# tongue_electrode_grid.net
KiCad netlist of a schematic drawn in EAGLE
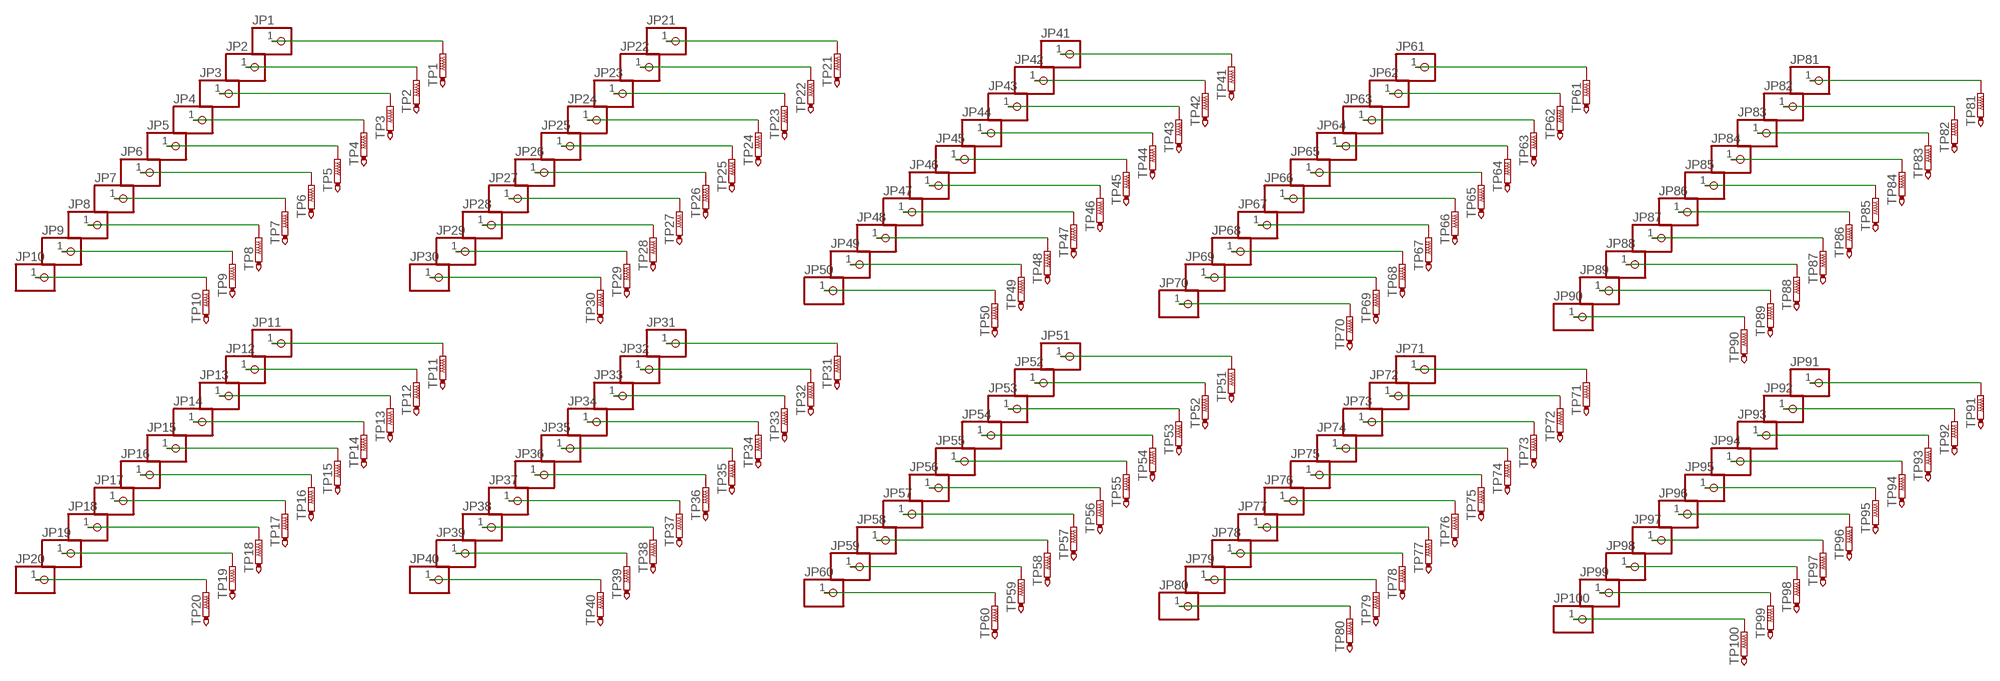
[diagram p0: schematic, sheet 1]

(export (version "E")
  (design (tool "Eeschema 10.0.6"))
  (components
    (comp (ref "JP1")
      (value "PINHD-1X1")
      (footprint "eagle-import:1X01")
      (libsource (lib "eagle-import") (part "PINHD-1X1"))
    )
    (comp (ref "JP2")
      (value "PINHD-1X1")
      (footprint "eagle-import:1X01")
      (libsource (lib "eagle-import") (part "PINHD-1X1"))
    )
    (comp (ref "JP3")
      (value "PINHD-1X1")
      (footprint "eagle-import:1X01")
      (libsource (lib "eagle-import") (part "PINHD-1X1"))
    )
    (comp (ref "JP4")
      (value "PINHD-1X1")
      (footprint "eagle-import:1X01")
      (libsource (lib "eagle-import") (part "PINHD-1X1"))
    )
    (comp (ref "JP5")
      (value "PINHD-1X1")
      (footprint "eagle-import:1X01")
      (libsource (lib "eagle-import") (part "PINHD-1X1"))
    )
    (comp (ref "JP6")
      (value "PINHD-1X1")
      (footprint "eagle-import:1X01")
      (libsource (lib "eagle-import") (part "PINHD-1X1"))
    )
    (comp (ref "JP7")
      (value "PINHD-1X1")
      (footprint "eagle-import:1X01")
      (libsource (lib "eagle-import") (part "PINHD-1X1"))
    )
    (comp (ref "JP8")
      (value "PINHD-1X1")
      (footprint "eagle-import:1X01")
      (libsource (lib "eagle-import") (part "PINHD-1X1"))
    )
    (comp (ref "JP9")
      (value "PINHD-1X1")
      (footprint "eagle-import:1X01")
      (libsource (lib "eagle-import") (part "PINHD-1X1"))
    )
    (comp (ref "JP10")
      (value "PINHD-1X1")
      (footprint "eagle-import:1X01")
      (libsource (lib "eagle-import") (part "PINHD-1X1"))
    )
    (comp (ref "JP11")
      (value "PINHD-1X1")
      (footprint "eagle-import:1X01")
      (libsource (lib "eagle-import") (part "PINHD-1X1"))
    )
    (comp (ref "JP12")
      (value "PINHD-1X1")
      (footprint "eagle-import:1X01")
      (libsource (lib "eagle-import") (part "PINHD-1X1"))
    )
    (comp (ref "JP13")
      (value "PINHD-1X1")
      (footprint "eagle-import:1X01")
      (libsource (lib "eagle-import") (part "PINHD-1X1"))
    )
    (comp (ref "JP14")
      (value "PINHD-1X1")
      (footprint "eagle-import:1X01")
      (libsource (lib "eagle-import") (part "PINHD-1X1"))
    )
    (comp (ref "JP15")
      (value "PINHD-1X1")
      (footprint "eagle-import:1X01")
      (libsource (lib "eagle-import") (part "PINHD-1X1"))
    )
    (comp (ref "JP16")
      (value "PINHD-1X1")
      (footprint "eagle-import:1X01")
      (libsource (lib "eagle-import") (part "PINHD-1X1"))
    )
    (comp (ref "JP17")
      (value "PINHD-1X1")
      (footprint "eagle-import:1X01")
      (libsource (lib "eagle-import") (part "PINHD-1X1"))
    )
    (comp (ref "JP18")
      (value "PINHD-1X1")
      (footprint "eagle-import:1X01")
      (libsource (lib "eagle-import") (part "PINHD-1X1"))
    )
    (comp (ref "JP19")
      (value "PINHD-1X1")
      (footprint "eagle-import:1X01")
      (libsource (lib "eagle-import") (part "PINHD-1X1"))
    )
    (comp (ref "JP20")
      (value "PINHD-1X1")
      (footprint "eagle-import:1X01")
      (libsource (lib "eagle-import") (part "PINHD-1X1"))
    )
    (comp (ref "JP21")
      (value "PINHD-1X1")
      (footprint "eagle-import:1X01")
      (libsource (lib "eagle-import") (part "PINHD-1X1"))
    )
    (comp (ref "JP22")
      (value "PINHD-1X1")
      (footprint "eagle-import:1X01")
      (libsource (lib "eagle-import") (part "PINHD-1X1"))
    )
    (comp (ref "JP23")
      (value "PINHD-1X1")
      (footprint "eagle-import:1X01")
      (libsource (lib "eagle-import") (part "PINHD-1X1"))
    )
    (comp (ref "JP24")
      (value "PINHD-1X1")
      (footprint "eagle-import:1X01")
      (libsource (lib "eagle-import") (part "PINHD-1X1"))
    )
    (comp (ref "JP25")
      (value "PINHD-1X1")
      (footprint "eagle-import:1X01")
      (libsource (lib "eagle-import") (part "PINHD-1X1"))
    )
    (comp (ref "JP26")
      (value "PINHD-1X1")
      (footprint "eagle-import:1X01")
      (libsource (lib "eagle-import") (part "PINHD-1X1"))
    )
    (comp (ref "JP27")
      (value "PINHD-1X1")
      (footprint "eagle-import:1X01")
      (libsource (lib "eagle-import") (part "PINHD-1X1"))
    )
    (comp (ref "JP28")
      (value "PINHD-1X1")
      (footprint "eagle-import:1X01")
      (libsource (lib "eagle-import") (part "PINHD-1X1"))
    )
    (comp (ref "JP29")
      (value "PINHD-1X1")
      (footprint "eagle-import:1X01")
      (libsource (lib "eagle-import") (part "PINHD-1X1"))
    )
    (comp (ref "JP30")
      (value "PINHD-1X1")
      (footprint "eagle-import:1X01")
      (libsource (lib "eagle-import") (part "PINHD-1X1"))
    )
    (comp (ref "JP31")
      (value "PINHD-1X1")
      (footprint "eagle-import:1X01")
      (libsource (lib "eagle-import") (part "PINHD-1X1"))
    )
    (comp (ref "JP32")
      (value "PINHD-1X1")
      (footprint "eagle-import:1X01")
      (libsource (lib "eagle-import") (part "PINHD-1X1"))
    )
    (comp (ref "JP33")
      (value "PINHD-1X1")
      (footprint "eagle-import:1X01")
      (libsource (lib "eagle-import") (part "PINHD-1X1"))
    )
    (comp (ref "JP34")
      (value "PINHD-1X1")
      (footprint "eagle-import:1X01")
      (libsource (lib "eagle-import") (part "PINHD-1X1"))
    )
    (comp (ref "JP35")
      (value "PINHD-1X1")
      (footprint "eagle-import:1X01")
      (libsource (lib "eagle-import") (part "PINHD-1X1"))
    )
    (comp (ref "JP36")
      (value "PINHD-1X1")
      (footprint "eagle-import:1X01")
      (libsource (lib "eagle-import") (part "PINHD-1X1"))
    )
    (comp (ref "JP37")
      (value "PINHD-1X1")
      (footprint "eagle-import:1X01")
      (libsource (lib "eagle-import") (part "PINHD-1X1"))
    )
    (comp (ref "JP38")
      (value "PINHD-1X1")
      (footprint "eagle-import:1X01")
      (libsource (lib "eagle-import") (part "PINHD-1X1"))
    )
    (comp (ref "JP39")
      (value "PINHD-1X1")
      (footprint "eagle-import:1X01")
      (libsource (lib "eagle-import") (part "PINHD-1X1"))
    )
    (comp (ref "JP40")
      (value "PINHD-1X1")
      (footprint "eagle-import:1X01")
      (libsource (lib "eagle-import") (part "PINHD-1X1"))
    )
    (comp (ref "JP41")
      (value "PINHD-1X1")
      (footprint "eagle-import:1X01")
      (libsource (lib "eagle-import") (part "PINHD-1X1"))
    )
    (comp (ref "JP42")
      (value "PINHD-1X1")
      (footprint "eagle-import:1X01")
      (libsource (lib "eagle-import") (part "PINHD-1X1"))
    )
    (comp (ref "JP43")
      (value "PINHD-1X1")
      (footprint "eagle-import:1X01")
      (libsource (lib "eagle-import") (part "PINHD-1X1"))
    )
    (comp (ref "JP44")
      (value "PINHD-1X1")
      (footprint "eagle-import:1X01")
      (libsource (lib "eagle-import") (part "PINHD-1X1"))
    )
    (comp (ref "JP45")
      (value "PINHD-1X1")
      (footprint "eagle-import:1X01")
      (libsource (lib "eagle-import") (part "PINHD-1X1"))
    )
    (comp (ref "JP46")
      (value "PINHD-1X1")
      (footprint "eagle-import:1X01")
      (libsource (lib "eagle-import") (part "PINHD-1X1"))
    )
    (comp (ref "JP47")
      (value "PINHD-1X1")
      (footprint "eagle-import:1X01")
      (libsource (lib "eagle-import") (part "PINHD-1X1"))
    )
    (comp (ref "JP48")
      (value "PINHD-1X1")
      (footprint "eagle-import:1X01")
      (libsource (lib "eagle-import") (part "PINHD-1X1"))
    )
    (comp (ref "JP49")
      (value "PINHD-1X1")
      (footprint "eagle-import:1X01")
      (libsource (lib "eagle-import") (part "PINHD-1X1"))
    )
    (comp (ref "JP50")
      (value "PINHD-1X1")
      (footprint "eagle-import:1X01")
      (libsource (lib "eagle-import") (part "PINHD-1X1"))
    )
    (comp (ref "JP51")
      (value "PINHD-1X1")
      (footprint "eagle-import:1X01")
      (libsource (lib "eagle-import") (part "PINHD-1X1"))
    )
    (comp (ref "JP52")
      (value "PINHD-1X1")
      (footprint "eagle-import:1X01")
      (libsource (lib "eagle-import") (part "PINHD-1X1"))
    )
    (comp (ref "JP53")
      (value "PINHD-1X1")
      (footprint "eagle-import:1X01")
      (libsource (lib "eagle-import") (part "PINHD-1X1"))
    )
    (comp (ref "JP54")
      (value "PINHD-1X1")
      (footprint "eagle-import:1X01")
      (libsource (lib "eagle-import") (part "PINHD-1X1"))
    )
    (comp (ref "JP55")
      (value "PINHD-1X1")
      (footprint "eagle-import:1X01")
      (libsource (lib "eagle-import") (part "PINHD-1X1"))
    )
    (comp (ref "JP56")
      (value "PINHD-1X1")
      (footprint "eagle-import:1X01")
      (libsource (lib "eagle-import") (part "PINHD-1X1"))
    )
    (comp (ref "JP57")
      (value "PINHD-1X1")
      (footprint "eagle-import:1X01")
      (libsource (lib "eagle-import") (part "PINHD-1X1"))
    )
    (comp (ref "JP58")
      (value "PINHD-1X1")
      (footprint "eagle-import:1X01")
      (libsource (lib "eagle-import") (part "PINHD-1X1"))
    )
    (comp (ref "JP59")
      (value "PINHD-1X1")
      (footprint "eagle-import:1X01")
      (libsource (lib "eagle-import") (part "PINHD-1X1"))
    )
    (comp (ref "JP60")
      (value "PINHD-1X1")
      (footprint "eagle-import:1X01")
      (libsource (lib "eagle-import") (part "PINHD-1X1"))
    )
    (comp (ref "JP61")
      (value "PINHD-1X1")
      (footprint "eagle-import:1X01")
      (libsource (lib "eagle-import") (part "PINHD-1X1"))
    )
    (comp (ref "JP62")
      (value "PINHD-1X1")
      (footprint "eagle-import:1X01")
      (libsource (lib "eagle-import") (part "PINHD-1X1"))
    )
    (comp (ref "JP63")
      (value "PINHD-1X1")
      (footprint "eagle-import:1X01")
      (libsource (lib "eagle-import") (part "PINHD-1X1"))
    )
    (comp (ref "JP64")
      (value "PINHD-1X1")
      (footprint "eagle-import:1X01")
      (libsource (lib "eagle-import") (part "PINHD-1X1"))
    )
    (comp (ref "JP65")
      (value "PINHD-1X1")
      (footprint "eagle-import:1X01")
      (libsource (lib "eagle-import") (part "PINHD-1X1"))
    )
    (comp (ref "JP66")
      (value "PINHD-1X1")
      (footprint "eagle-import:1X01")
      (libsource (lib "eagle-import") (part "PINHD-1X1"))
    )
    (comp (ref "JP67")
      (value "PINHD-1X1")
      (footprint "eagle-import:1X01")
      (libsource (lib "eagle-import") (part "PINHD-1X1"))
    )
    (comp (ref "JP68")
      (value "PINHD-1X1")
      (footprint "eagle-import:1X01")
      (libsource (lib "eagle-import") (part "PINHD-1X1"))
    )
    (comp (ref "JP69")
      (value "PINHD-1X1")
      (footprint "eagle-import:1X01")
      (libsource (lib "eagle-import") (part "PINHD-1X1"))
    )
    (comp (ref "JP70")
      (value "PINHD-1X1")
      (footprint "eagle-import:1X01")
      (libsource (lib "eagle-import") (part "PINHD-1X1"))
    )
    (comp (ref "JP71")
      (value "PINHD-1X1")
      (footprint "eagle-import:1X01")
      (libsource (lib "eagle-import") (part "PINHD-1X1"))
    )
    (comp (ref "JP72")
      (value "PINHD-1X1")
      (footprint "eagle-import:1X01")
      (libsource (lib "eagle-import") (part "PINHD-1X1"))
    )
    (comp (ref "JP73")
      (value "PINHD-1X1")
      (footprint "eagle-import:1X01")
      (libsource (lib "eagle-import") (part "PINHD-1X1"))
    )
    (comp (ref "JP74")
      (value "PINHD-1X1")
      (footprint "eagle-import:1X01")
      (libsource (lib "eagle-import") (part "PINHD-1X1"))
    )
    (comp (ref "JP75")
      (value "PINHD-1X1")
      (footprint "eagle-import:1X01")
      (libsource (lib "eagle-import") (part "PINHD-1X1"))
    )
    (comp (ref "JP76")
      (value "PINHD-1X1")
      (footprint "eagle-import:1X01")
      (libsource (lib "eagle-import") (part "PINHD-1X1"))
    )
    (comp (ref "JP77")
      (value "PINHD-1X1")
      (footprint "eagle-import:1X01")
      (libsource (lib "eagle-import") (part "PINHD-1X1"))
    )
    (comp (ref "JP78")
      (value "PINHD-1X1")
      (footprint "eagle-import:1X01")
      (libsource (lib "eagle-import") (part "PINHD-1X1"))
    )
    (comp (ref "JP79")
      (value "PINHD-1X1")
      (footprint "eagle-import:1X01")
      (libsource (lib "eagle-import") (part "PINHD-1X1"))
    )
    (comp (ref "JP80")
      (value "PINHD-1X1")
      (footprint "eagle-import:1X01")
      (libsource (lib "eagle-import") (part "PINHD-1X1"))
    )
    (comp (ref "JP81")
      (value "PINHD-1X1")
      (footprint "eagle-import:1X01")
      (libsource (lib "eagle-import") (part "PINHD-1X1"))
    )
    (comp (ref "JP82")
      (value "PINHD-1X1")
      (footprint "eagle-import:1X01")
      (libsource (lib "eagle-import") (part "PINHD-1X1"))
    )
    (comp (ref "JP83")
      (value "PINHD-1X1")
      (footprint "eagle-import:1X01")
      (libsource (lib "eagle-import") (part "PINHD-1X1"))
    )
    (comp (ref "JP84")
      (value "PINHD-1X1")
      (footprint "eagle-import:1X01")
      (libsource (lib "eagle-import") (part "PINHD-1X1"))
    )
    (comp (ref "JP85")
      (value "PINHD-1X1")
      (footprint "eagle-import:1X01")
      (libsource (lib "eagle-import") (part "PINHD-1X1"))
    )
    (comp (ref "JP86")
      (value "PINHD-1X1")
      (footprint "eagle-import:1X01")
      (libsource (lib "eagle-import") (part "PINHD-1X1"))
    )
    (comp (ref "JP87")
      (value "PINHD-1X1")
      (footprint "eagle-import:1X01")
      (libsource (lib "eagle-import") (part "PINHD-1X1"))
    )
    (comp (ref "JP88")
      (value "PINHD-1X1")
      (footprint "eagle-import:1X01")
      (libsource (lib "eagle-import") (part "PINHD-1X1"))
    )
    (comp (ref "JP89")
      (value "PINHD-1X1")
      (footprint "eagle-import:1X01")
      (libsource (lib "eagle-import") (part "PINHD-1X1"))
    )
    (comp (ref "JP90")
      (value "PINHD-1X1")
      (footprint "eagle-import:1X01")
      (libsource (lib "eagle-import") (part "PINHD-1X1"))
    )
    (comp (ref "JP91")
      (value "PINHD-1X1")
      (footprint "eagle-import:1X01")
      (libsource (lib "eagle-import") (part "PINHD-1X1"))
    )
    (comp (ref "JP92")
      (value "PINHD-1X1")
      (footprint "eagle-import:1X01")
      (libsource (lib "eagle-import") (part "PINHD-1X1"))
    )
    (comp (ref "JP93")
      (value "PINHD-1X1")
      (footprint "eagle-import:1X01")
      (libsource (lib "eagle-import") (part "PINHD-1X1"))
    )
    (comp (ref "JP94")
      (value "PINHD-1X1")
      (footprint "eagle-import:1X01")
      (libsource (lib "eagle-import") (part "PINHD-1X1"))
    )
    (comp (ref "JP95")
      (value "PINHD-1X1")
      (footprint "eagle-import:1X01")
      (libsource (lib "eagle-import") (part "PINHD-1X1"))
    )
    (comp (ref "JP96")
      (value "PINHD-1X1")
      (footprint "eagle-import:1X01")
      (libsource (lib "eagle-import") (part "PINHD-1X1"))
    )
    (comp (ref "JP97")
      (value "PINHD-1X1")
      (footprint "eagle-import:1X01")
      (libsource (lib "eagle-import") (part "PINHD-1X1"))
    )
    (comp (ref "JP98")
      (value "PINHD-1X1")
      (footprint "eagle-import:1X01")
      (libsource (lib "eagle-import") (part "PINHD-1X1"))
    )
    (comp (ref "JP99")
      (value "PINHD-1X1")
      (footprint "eagle-import:1X01")
      (libsource (lib "eagle-import") (part "PINHD-1X1"))
    )
    (comp (ref "JP100")
      (value "PINHD-1X1")
      (footprint "eagle-import:1X01")
      (libsource (lib "eagle-import") (part "PINHD-1X1"))
    )
    (comp (ref "TP1")
      (value "PTR1TP11R")
      (footprint "eagle-import:TP11R")
      (libsource (lib "eagle-import") (part "PTR1TP11R"))
    )
    (comp (ref "TP2")
      (value "PTR1TP11R")
      (footprint "eagle-import:TP11R")
      (libsource (lib "eagle-import") (part "PTR1TP11R"))
    )
    (comp (ref "TP3")
      (value "PTR1TP11R")
      (footprint "eagle-import:TP11R")
      (libsource (lib "eagle-import") (part "PTR1TP11R"))
    )
    (comp (ref "TP4")
      (value "PTR1TP11R")
      (footprint "eagle-import:TP11R")
      (libsource (lib "eagle-import") (part "PTR1TP11R"))
    )
    (comp (ref "TP5")
      (value "PTR1TP11R")
      (footprint "eagle-import:TP11R")
      (libsource (lib "eagle-import") (part "PTR1TP11R"))
    )
    (comp (ref "TP6")
      (value "PTR1TP11R")
      (footprint "eagle-import:TP11R")
      (libsource (lib "eagle-import") (part "PTR1TP11R"))
    )
    (comp (ref "TP7")
      (value "PTR1TP11R")
      (footprint "eagle-import:TP11R")
      (libsource (lib "eagle-import") (part "PTR1TP11R"))
    )
    (comp (ref "TP8")
      (value "PTR1TP11R")
      (footprint "eagle-import:TP11R")
      (libsource (lib "eagle-import") (part "PTR1TP11R"))
    )
    (comp (ref "TP9")
      (value "PTR1TP11R")
      (footprint "eagle-import:TP11R")
      (libsource (lib "eagle-import") (part "PTR1TP11R"))
    )
    (comp (ref "TP10")
      (value "PTR1TP11R")
      (footprint "eagle-import:TP11R")
      (libsource (lib "eagle-import") (part "PTR1TP11R"))
    )
    (comp (ref "TP11")
      (value "PTR1TP11R")
      (footprint "eagle-import:TP11R")
      (libsource (lib "eagle-import") (part "PTR1TP11R"))
    )
    (comp (ref "TP12")
      (value "PTR1TP11R")
      (footprint "eagle-import:TP11R")
      (libsource (lib "eagle-import") (part "PTR1TP11R"))
    )
    (comp (ref "TP13")
      (value "PTR1TP11R")
      (footprint "eagle-import:TP11R")
      (libsource (lib "eagle-import") (part "PTR1TP11R"))
    )
    (comp (ref "TP14")
      (value "PTR1TP11R")
      (footprint "eagle-import:TP11R")
      (libsource (lib "eagle-import") (part "PTR1TP11R"))
    )
    (comp (ref "TP15")
      (value "PTR1TP11R")
      (footprint "eagle-import:TP11R")
      (libsource (lib "eagle-import") (part "PTR1TP11R"))
    )
    (comp (ref "TP16")
      (value "PTR1TP11R")
      (footprint "eagle-import:TP11R")
      (libsource (lib "eagle-import") (part "PTR1TP11R"))
    )
    (comp (ref "TP17")
      (value "PTR1TP11R")
      (footprint "eagle-import:TP11R")
      (libsource (lib "eagle-import") (part "PTR1TP11R"))
    )
    (comp (ref "TP18")
      (value "PTR1TP11R")
      (footprint "eagle-import:TP11R")
      (libsource (lib "eagle-import") (part "PTR1TP11R"))
    )
    (comp (ref "TP19")
      (value "PTR1TP11R")
      (footprint "eagle-import:TP11R")
      (libsource (lib "eagle-import") (part "PTR1TP11R"))
    )
    (comp (ref "TP20")
      (value "PTR1TP11R")
      (footprint "eagle-import:TP11R")
      (libsource (lib "eagle-import") (part "PTR1TP11R"))
    )
    (comp (ref "TP21")
      (value "PTR1TP11R")
      (footprint "eagle-import:TP11R")
      (libsource (lib "eagle-import") (part "PTR1TP11R"))
    )
    (comp (ref "TP22")
      (value "PTR1TP11R")
      (footprint "eagle-import:TP11R")
      (libsource (lib "eagle-import") (part "PTR1TP11R"))
    )
    (comp (ref "TP23")
      (value "PTR1TP11R")
      (footprint "eagle-import:TP11R")
      (libsource (lib "eagle-import") (part "PTR1TP11R"))
    )
    (comp (ref "TP24")
      (value "PTR1TP11R")
      (footprint "eagle-import:TP11R")
      (libsource (lib "eagle-import") (part "PTR1TP11R"))
    )
    (comp (ref "TP25")
      (value "PTR1TP11R")
      (footprint "eagle-import:TP11R")
      (libsource (lib "eagle-import") (part "PTR1TP11R"))
    )
    (comp (ref "TP26")
      (value "PTR1TP11R")
      (footprint "eagle-import:TP11R")
      (libsource (lib "eagle-import") (part "PTR1TP11R"))
    )
    (comp (ref "TP27")
      (value "PTR1TP11R")
      (footprint "eagle-import:TP11R")
      (libsource (lib "eagle-import") (part "PTR1TP11R"))
    )
    (comp (ref "TP28")
      (value "PTR1TP11R")
      (footprint "eagle-import:TP11R")
      (libsource (lib "eagle-import") (part "PTR1TP11R"))
    )
    (comp (ref "TP29")
      (value "PTR1TP11R")
      (footprint "eagle-import:TP11R")
      (libsource (lib "eagle-import") (part "PTR1TP11R"))
    )
    (comp (ref "TP30")
      (value "PTR1TP11R")
      (footprint "eagle-import:TP11R")
      (libsource (lib "eagle-import") (part "PTR1TP11R"))
    )
    (comp (ref "TP31")
      (value "PTR1TP11R")
      (footprint "eagle-import:TP11R")
      (libsource (lib "eagle-import") (part "PTR1TP11R"))
    )
    (comp (ref "TP32")
      (value "PTR1TP11R")
      (footprint "eagle-import:TP11R")
      (libsource (lib "eagle-import") (part "PTR1TP11R"))
    )
    (comp (ref "TP33")
      (value "PTR1TP11R")
      (footprint "eagle-import:TP11R")
      (libsource (lib "eagle-import") (part "PTR1TP11R"))
    )
    (comp (ref "TP34")
      (value "PTR1TP11R")
      (footprint "eagle-import:TP11R")
      (libsource (lib "eagle-import") (part "PTR1TP11R"))
    )
    (comp (ref "TP35")
      (value "PTR1TP11R")
      (footprint "eagle-import:TP11R")
      (libsource (lib "eagle-import") (part "PTR1TP11R"))
    )
    (comp (ref "TP36")
      (value "PTR1TP11R")
      (footprint "eagle-import:TP11R")
      (libsource (lib "eagle-import") (part "PTR1TP11R"))
    )
    (comp (ref "TP37")
      (value "PTR1TP11R")
      (footprint "eagle-import:TP11R")
      (libsource (lib "eagle-import") (part "PTR1TP11R"))
    )
    (comp (ref "TP38")
      (value "PTR1TP11R")
      (footprint "eagle-import:TP11R")
      (libsource (lib "eagle-import") (part "PTR1TP11R"))
    )
    (comp (ref "TP39")
      (value "PTR1TP11R")
      (footprint "eagle-import:TP11R")
      (libsource (lib "eagle-import") (part "PTR1TP11R"))
    )
    (comp (ref "TP40")
      (value "PTR1TP11R")
      (footprint "eagle-import:TP11R")
      (libsource (lib "eagle-import") (part "PTR1TP11R"))
    )
    (comp (ref "TP41")
      (value "PTR1TP11R")
      (footprint "eagle-import:TP11R")
      (libsource (lib "eagle-import") (part "PTR1TP11R"))
    )
    (comp (ref "TP42")
      (value "PTR1TP11R")
      (footprint "eagle-import:TP11R")
      (libsource (lib "eagle-import") (part "PTR1TP11R"))
    )
    (comp (ref "TP43")
      (value "PTR1TP11R")
      (footprint "eagle-import:TP11R")
      (libsource (lib "eagle-import") (part "PTR1TP11R"))
    )
    (comp (ref "TP44")
      (value "PTR1TP11R")
      (footprint "eagle-import:TP11R")
      (libsource (lib "eagle-import") (part "PTR1TP11R"))
    )
    (comp (ref "TP45")
      (value "PTR1TP11R")
      (footprint "eagle-import:TP11R")
      (libsource (lib "eagle-import") (part "PTR1TP11R"))
    )
    (comp (ref "TP46")
      (value "PTR1TP11R")
      (footprint "eagle-import:TP11R")
      (libsource (lib "eagle-import") (part "PTR1TP11R"))
    )
    (comp (ref "TP47")
      (value "PTR1TP11R")
      (footprint "eagle-import:TP11R")
      (libsource (lib "eagle-import") (part "PTR1TP11R"))
    )
    (comp (ref "TP48")
      (value "PTR1TP11R")
      (footprint "eagle-import:TP11R")
      (libsource (lib "eagle-import") (part "PTR1TP11R"))
    )
    (comp (ref "TP49")
      (value "PTR1TP11R")
      (footprint "eagle-import:TP11R")
      (libsource (lib "eagle-import") (part "PTR1TP11R"))
    )
    (comp (ref "TP50")
      (value "PTR1TP11R")
      (footprint "eagle-import:TP11R")
      (libsource (lib "eagle-import") (part "PTR1TP11R"))
    )
    (comp (ref "TP51")
      (value "PTR1TP11R")
      (footprint "eagle-import:TP11R")
      (libsource (lib "eagle-import") (part "PTR1TP11R"))
    )
    (comp (ref "TP52")
      (value "PTR1TP11R")
      (footprint "eagle-import:TP11R")
      (libsource (lib "eagle-import") (part "PTR1TP11R"))
    )
    (comp (ref "TP53")
      (value "PTR1TP11R")
      (footprint "eagle-import:TP11R")
      (libsource (lib "eagle-import") (part "PTR1TP11R"))
    )
    (comp (ref "TP54")
      (value "PTR1TP11R")
      (footprint "eagle-import:TP11R")
      (libsource (lib "eagle-import") (part "PTR1TP11R"))
    )
    (comp (ref "TP55")
      (value "PTR1TP11R")
      (footprint "eagle-import:TP11R")
      (libsource (lib "eagle-import") (part "PTR1TP11R"))
    )
    (comp (ref "TP56")
      (value "PTR1TP11R")
      (footprint "eagle-import:TP11R")
      (libsource (lib "eagle-import") (part "PTR1TP11R"))
    )
    (comp (ref "TP57")
      (value "PTR1TP11R")
      (footprint "eagle-import:TP11R")
      (libsource (lib "eagle-import") (part "PTR1TP11R"))
    )
    (comp (ref "TP58")
      (value "PTR1TP11R")
      (footprint "eagle-import:TP11R")
      (libsource (lib "eagle-import") (part "PTR1TP11R"))
    )
    (comp (ref "TP59")
      (value "PTR1TP11R")
      (footprint "eagle-import:TP11R")
      (libsource (lib "eagle-import") (part "PTR1TP11R"))
    )
    (comp (ref "TP60")
      (value "PTR1TP11R")
      (footprint "eagle-import:TP11R")
      (libsource (lib "eagle-import") (part "PTR1TP11R"))
    )
    (comp (ref "TP61")
      (value "PTR1TP11R")
      (footprint "eagle-import:TP11R")
      (libsource (lib "eagle-import") (part "PTR1TP11R"))
    )
    (comp (ref "TP62")
      (value "PTR1TP11R")
      (footprint "eagle-import:TP11R")
      (libsource (lib "eagle-import") (part "PTR1TP11R"))
    )
    (comp (ref "TP63")
      (value "PTR1TP11R")
      (footprint "eagle-import:TP11R")
      (libsource (lib "eagle-import") (part "PTR1TP11R"))
    )
    (comp (ref "TP64")
      (value "PTR1TP11R")
      (footprint "eagle-import:TP11R")
      (libsource (lib "eagle-import") (part "PTR1TP11R"))
    )
    (comp (ref "TP65")
      (value "PTR1TP11R")
      (footprint "eagle-import:TP11R")
      (libsource (lib "eagle-import") (part "PTR1TP11R"))
    )
    (comp (ref "TP66")
      (value "PTR1TP11R")
      (footprint "eagle-import:TP11R")
      (libsource (lib "eagle-import") (part "PTR1TP11R"))
    )
    (comp (ref "TP67")
      (value "PTR1TP11R")
      (footprint "eagle-import:TP11R")
      (libsource (lib "eagle-import") (part "PTR1TP11R"))
    )
    (comp (ref "TP68")
      (value "PTR1TP11R")
      (footprint "eagle-import:TP11R")
      (libsource (lib "eagle-import") (part "PTR1TP11R"))
    )
    (comp (ref "TP69")
      (value "PTR1TP11R")
      (footprint "eagle-import:TP11R")
      (libsource (lib "eagle-import") (part "PTR1TP11R"))
    )
    (comp (ref "TP70")
      (value "PTR1TP11R")
      (footprint "eagle-import:TP11R")
      (libsource (lib "eagle-import") (part "PTR1TP11R"))
    )
    (comp (ref "TP71")
      (value "PTR1TP11R")
      (footprint "eagle-import:TP11R")
      (libsource (lib "eagle-import") (part "PTR1TP11R"))
    )
    (comp (ref "TP72")
      (value "PTR1TP11R")
      (footprint "eagle-import:TP11R")
      (libsource (lib "eagle-import") (part "PTR1TP11R"))
    )
    (comp (ref "TP73")
      (value "PTR1TP11R")
      (footprint "eagle-import:TP11R")
      (libsource (lib "eagle-import") (part "PTR1TP11R"))
    )
    (comp (ref "TP74")
      (value "PTR1TP11R")
      (footprint "eagle-import:TP11R")
      (libsource (lib "eagle-import") (part "PTR1TP11R"))
    )
    (comp (ref "TP75")
      (value "PTR1TP11R")
      (footprint "eagle-import:TP11R")
      (libsource (lib "eagle-import") (part "PTR1TP11R"))
    )
    (comp (ref "TP76")
      (value "PTR1TP11R")
      (footprint "eagle-import:TP11R")
      (libsource (lib "eagle-import") (part "PTR1TP11R"))
    )
    (comp (ref "TP77")
      (value "PTR1TP11R")
      (footprint "eagle-import:TP11R")
      (libsource (lib "eagle-import") (part "PTR1TP11R"))
    )
    (comp (ref "TP78")
      (value "PTR1TP11R")
      (footprint "eagle-import:TP11R")
      (libsource (lib "eagle-import") (part "PTR1TP11R"))
    )
    (comp (ref "TP79")
      (value "PTR1TP11R")
      (footprint "eagle-import:TP11R")
      (libsource (lib "eagle-import") (part "PTR1TP11R"))
    )
    (comp (ref "TP80")
      (value "PTR1TP11R")
      (footprint "eagle-import:TP11R")
      (libsource (lib "eagle-import") (part "PTR1TP11R"))
    )
    (comp (ref "TP81")
      (value "PTR1TP11R")
      (footprint "eagle-import:TP11R")
      (libsource (lib "eagle-import") (part "PTR1TP11R"))
    )
    (comp (ref "TP82")
      (value "PTR1TP11R")
      (footprint "eagle-import:TP11R")
      (libsource (lib "eagle-import") (part "PTR1TP11R"))
    )
    (comp (ref "TP83")
      (value "PTR1TP11R")
      (footprint "eagle-import:TP11R")
      (libsource (lib "eagle-import") (part "PTR1TP11R"))
    )
    (comp (ref "TP84")
      (value "PTR1TP11R")
      (footprint "eagle-import:TP11R")
      (libsource (lib "eagle-import") (part "PTR1TP11R"))
    )
    (comp (ref "TP85")
      (value "PTR1TP11R")
      (footprint "eagle-import:TP11R")
      (libsource (lib "eagle-import") (part "PTR1TP11R"))
    )
    (comp (ref "TP86")
      (value "PTR1TP11R")
      (footprint "eagle-import:TP11R")
      (libsource (lib "eagle-import") (part "PTR1TP11R"))
    )
    (comp (ref "TP87")
      (value "PTR1TP11R")
      (footprint "eagle-import:TP11R")
      (libsource (lib "eagle-import") (part "PTR1TP11R"))
    )
    (comp (ref "TP88")
      (value "PTR1TP11R")
      (footprint "eagle-import:TP11R")
      (libsource (lib "eagle-import") (part "PTR1TP11R"))
    )
    (comp (ref "TP89")
      (value "PTR1TP11R")
      (footprint "eagle-import:TP11R")
      (libsource (lib "eagle-import") (part "PTR1TP11R"))
    )
    (comp (ref "TP90")
      (value "PTR1TP11R")
      (footprint "eagle-import:TP11R")
      (libsource (lib "eagle-import") (part "PTR1TP11R"))
    )
    (comp (ref "TP91")
      (value "PTR1TP11R")
      (footprint "eagle-import:TP11R")
      (libsource (lib "eagle-import") (part "PTR1TP11R"))
    )
    (comp (ref "TP92")
      (value "PTR1TP11R")
      (footprint "eagle-import:TP11R")
      (libsource (lib "eagle-import") (part "PTR1TP11R"))
    )
    (comp (ref "TP93")
      (value "PTR1TP11R")
      (footprint "eagle-import:TP11R")
      (libsource (lib "eagle-import") (part "PTR1TP11R"))
    )
    (comp (ref "TP94")
      (value "PTR1TP11R")
      (footprint "eagle-import:TP11R")
      (libsource (lib "eagle-import") (part "PTR1TP11R"))
    )
    (comp (ref "TP95")
      (value "PTR1TP11R")
      (footprint "eagle-import:TP11R")
      (libsource (lib "eagle-import") (part "PTR1TP11R"))
    )
    (comp (ref "TP96")
      (value "PTR1TP11R")
      (footprint "eagle-import:TP11R")
      (libsource (lib "eagle-import") (part "PTR1TP11R"))
    )
    (comp (ref "TP97")
      (value "PTR1TP11R")
      (footprint "eagle-import:TP11R")
      (libsource (lib "eagle-import") (part "PTR1TP11R"))
    )
    (comp (ref "TP98")
      (value "PTR1TP11R")
      (footprint "eagle-import:TP11R")
      (libsource (lib "eagle-import") (part "PTR1TP11R"))
    )
    (comp (ref "TP99")
      (value "PTR1TP11R")
      (footprint "eagle-import:TP11R")
      (libsource (lib "eagle-import") (part "PTR1TP11R"))
    )
    (comp (ref "TP100")
      (value "PTR1TP11R")
      (footprint "eagle-import:TP11R")
      (libsource (lib "eagle-import") (part "PTR1TP11R"))
    )
  )
  (nets
    (net (code "1") (name "Net-(JP1-Pad1)") (class "Default")
      (node (ref "JP1") (pin "1") (pinfunction "1_1") (pintype "passive"))
      (node (ref "TP1") (pin "TP") (pinfunction "TP_TP") (pintype "input"))
    )
    (net (code "2") (name "Net-(JP2-Pad1)") (class "Default")
      (node (ref "JP2") (pin "1") (pinfunction "1_1") (pintype "passive"))
      (node (ref "TP2") (pin "TP") (pinfunction "TP_TP") (pintype "input"))
    )
    (net (code "3") (name "Net-(JP3-Pad1)") (class "Default")
      (node (ref "JP3") (pin "1") (pinfunction "1_1") (pintype "passive"))
      (node (ref "TP3") (pin "TP") (pinfunction "TP_TP") (pintype "input"))
    )
    (net (code "4") (name "Net-(JP4-Pad1)") (class "Default")
      (node (ref "JP4") (pin "1") (pinfunction "1_1") (pintype "passive"))
      (node (ref "TP4") (pin "TP") (pinfunction "TP_TP") (pintype "input"))
    )
    (net (code "5") (name "Net-(JP5-Pad1)") (class "Default")
      (node (ref "JP5") (pin "1") (pinfunction "1_1") (pintype "passive"))
      (node (ref "TP5") (pin "TP") (pinfunction "TP_TP") (pintype "input"))
    )
    (net (code "6") (name "Net-(JP6-Pad1)") (class "Default")
      (node (ref "JP6") (pin "1") (pinfunction "1_1") (pintype "passive"))
      (node (ref "TP6") (pin "TP") (pinfunction "TP_TP") (pintype "input"))
    )
    (net (code "7") (name "Net-(JP7-Pad1)") (class "Default")
      (node (ref "JP7") (pin "1") (pinfunction "1_1") (pintype "passive"))
      (node (ref "TP7") (pin "TP") (pinfunction "TP_TP") (pintype "input"))
    )
    (net (code "8") (name "Net-(JP8-Pad1)") (class "Default")
      (node (ref "JP8") (pin "1") (pinfunction "1_1") (pintype "passive"))
      (node (ref "TP8") (pin "TP") (pinfunction "TP_TP") (pintype "input"))
    )
    (net (code "9") (name "Net-(JP9-Pad1)") (class "Default")
      (node (ref "JP9") (pin "1") (pinfunction "1_1") (pintype "passive"))
      (node (ref "TP9") (pin "TP") (pinfunction "TP_TP") (pintype "input"))
    )
    (net (code "10") (name "Net-(JP10-Pad1)") (class "Default")
      (node (ref "JP10") (pin "1") (pinfunction "1_1") (pintype "passive"))
      (node (ref "TP10") (pin "TP") (pinfunction "TP_TP") (pintype "input"))
    )
    (net (code "11") (name "Net-(JP11-Pad1)") (class "Default")
      (node (ref "JP11") (pin "1") (pinfunction "1_1") (pintype "passive"))
      (node (ref "TP11") (pin "TP") (pinfunction "TP_TP") (pintype "input"))
    )
    (net (code "12") (name "Net-(JP12-Pad1)") (class "Default")
      (node (ref "JP12") (pin "1") (pinfunction "1_1") (pintype "passive"))
      (node (ref "TP12") (pin "TP") (pinfunction "TP_TP") (pintype "input"))
    )
    (net (code "13") (name "Net-(JP13-Pad1)") (class "Default")
      (node (ref "JP13") (pin "1") (pinfunction "1_1") (pintype "passive"))
      (node (ref "TP13") (pin "TP") (pinfunction "TP_TP") (pintype "input"))
    )
    (net (code "14") (name "Net-(JP14-Pad1)") (class "Default")
      (node (ref "JP14") (pin "1") (pinfunction "1_1") (pintype "passive"))
      (node (ref "TP14") (pin "TP") (pinfunction "TP_TP") (pintype "input"))
    )
    (net (code "15") (name "Net-(JP15-Pad1)") (class "Default")
      (node (ref "JP15") (pin "1") (pinfunction "1_1") (pintype "passive"))
      (node (ref "TP15") (pin "TP") (pinfunction "TP_TP") (pintype "input"))
    )
    (net (code "16") (name "Net-(JP16-Pad1)") (class "Default")
      (node (ref "JP16") (pin "1") (pinfunction "1_1") (pintype "passive"))
      (node (ref "TP16") (pin "TP") (pinfunction "TP_TP") (pintype "input"))
    )
    (net (code "17") (name "Net-(JP17-Pad1)") (class "Default")
      (node (ref "JP17") (pin "1") (pinfunction "1_1") (pintype "passive"))
      (node (ref "TP17") (pin "TP") (pinfunction "TP_TP") (pintype "input"))
    )
    (net (code "18") (name "Net-(JP18-Pad1)") (class "Default")
      (node (ref "JP18") (pin "1") (pinfunction "1_1") (pintype "passive"))
      (node (ref "TP18") (pin "TP") (pinfunction "TP_TP") (pintype "input"))
    )
    (net (code "19") (name "Net-(JP19-Pad1)") (class "Default")
      (node (ref "JP19") (pin "1") (pinfunction "1_1") (pintype "passive"))
      (node (ref "TP19") (pin "TP") (pinfunction "TP_TP") (pintype "input"))
    )
    (net (code "20") (name "Net-(JP20-Pad1)") (class "Default")
      (node (ref "JP20") (pin "1") (pinfunction "1_1") (pintype "passive"))
      (node (ref "TP20") (pin "TP") (pinfunction "TP_TP") (pintype "input"))
    )
    (net (code "21") (name "Net-(JP21-Pad1)") (class "Default")
      (node (ref "JP21") (pin "1") (pinfunction "1_1") (pintype "passive"))
      (node (ref "TP21") (pin "TP") (pinfunction "TP_TP") (pintype "input"))
    )
    (net (code "22") (name "Net-(JP22-Pad1)") (class "Default")
      (node (ref "JP22") (pin "1") (pinfunction "1_1") (pintype "passive"))
      (node (ref "TP22") (pin "TP") (pinfunction "TP_TP") (pintype "input"))
    )
    (net (code "23") (name "Net-(JP23-Pad1)") (class "Default")
      (node (ref "JP23") (pin "1") (pinfunction "1_1") (pintype "passive"))
      (node (ref "TP23") (pin "TP") (pinfunction "TP_TP") (pintype "input"))
    )
    (net (code "24") (name "Net-(JP24-Pad1)") (class "Default")
      (node (ref "JP24") (pin "1") (pinfunction "1_1") (pintype "passive"))
      (node (ref "TP24") (pin "TP") (pinfunction "TP_TP") (pintype "input"))
    )
    (net (code "25") (name "Net-(JP25-Pad1)") (class "Default")
      (node (ref "JP25") (pin "1") (pinfunction "1_1") (pintype "passive"))
      (node (ref "TP25") (pin "TP") (pinfunction "TP_TP") (pintype "input"))
    )
    (net (code "26") (name "Net-(JP26-Pad1)") (class "Default")
      (node (ref "JP26") (pin "1") (pinfunction "1_1") (pintype "passive"))
      (node (ref "TP26") (pin "TP") (pinfunction "TP_TP") (pintype "input"))
    )
    (net (code "27") (name "Net-(JP27-Pad1)") (class "Default")
      (node (ref "JP27") (pin "1") (pinfunction "1_1") (pintype "passive"))
      (node (ref "TP27") (pin "TP") (pinfunction "TP_TP") (pintype "input"))
    )
    (net (code "28") (name "Net-(JP28-Pad1)") (class "Default")
      (node (ref "JP28") (pin "1") (pinfunction "1_1") (pintype "passive"))
      (node (ref "TP28") (pin "TP") (pinfunction "TP_TP") (pintype "input"))
    )
    (net (code "29") (name "Net-(JP29-Pad1)") (class "Default")
      (node (ref "JP29") (pin "1") (pinfunction "1_1") (pintype "passive"))
      (node (ref "TP29") (pin "TP") (pinfunction "TP_TP") (pintype "input"))
    )
    (net (code "30") (name "Net-(JP30-Pad1)") (class "Default")
      (node (ref "JP30") (pin "1") (pinfunction "1_1") (pintype "passive"))
      (node (ref "TP30") (pin "TP") (pinfunction "TP_TP") (pintype "input"))
    )
    (net (code "31") (name "Net-(JP31-Pad1)") (class "Default")
      (node (ref "JP31") (pin "1") (pinfunction "1_1") (pintype "passive"))
      (node (ref "TP31") (pin "TP") (pinfunction "TP_TP") (pintype "input"))
    )
    (net (code "32") (name "Net-(JP32-Pad1)") (class "Default")
      (node (ref "JP32") (pin "1") (pinfunction "1_1") (pintype "passive"))
      (node (ref "TP32") (pin "TP") (pinfunction "TP_TP") (pintype "input"))
    )
    (net (code "33") (name "Net-(JP33-Pad1)") (class "Default")
      (node (ref "JP33") (pin "1") (pinfunction "1_1") (pintype "passive"))
      (node (ref "TP33") (pin "TP") (pinfunction "TP_TP") (pintype "input"))
    )
    (net (code "34") (name "Net-(JP34-Pad1)") (class "Default")
      (node (ref "JP34") (pin "1") (pinfunction "1_1") (pintype "passive"))
      (node (ref "TP34") (pin "TP") (pinfunction "TP_TP") (pintype "input"))
    )
    (net (code "35") (name "Net-(JP35-Pad1)") (class "Default")
      (node (ref "JP35") (pin "1") (pinfunction "1_1") (pintype "passive"))
      (node (ref "TP35") (pin "TP") (pinfunction "TP_TP") (pintype "input"))
    )
    (net (code "36") (name "Net-(JP36-Pad1)") (class "Default")
      (node (ref "JP36") (pin "1") (pinfunction "1_1") (pintype "passive"))
      (node (ref "TP36") (pin "TP") (pinfunction "TP_TP") (pintype "input"))
    )
    (net (code "37") (name "Net-(JP37-Pad1)") (class "Default")
      (node (ref "JP37") (pin "1") (pinfunction "1_1") (pintype "passive"))
      (node (ref "TP37") (pin "TP") (pinfunction "TP_TP") (pintype "input"))
    )
    (net (code "38") (name "Net-(JP38-Pad1)") (class "Default")
      (node (ref "JP38") (pin "1") (pinfunction "1_1") (pintype "passive"))
      (node (ref "TP38") (pin "TP") (pinfunction "TP_TP") (pintype "input"))
    )
    (net (code "39") (name "Net-(JP39-Pad1)") (class "Default")
      (node (ref "JP39") (pin "1") (pinfunction "1_1") (pintype "passive"))
      (node (ref "TP39") (pin "TP") (pinfunction "TP_TP") (pintype "input"))
    )
    (net (code "40") (name "Net-(JP40-Pad1)") (class "Default")
      (node (ref "JP40") (pin "1") (pinfunction "1_1") (pintype "passive"))
      (node (ref "TP40") (pin "TP") (pinfunction "TP_TP") (pintype "input"))
    )
    (net (code "41") (name "Net-(JP41-Pad1)") (class "Default")
      (node (ref "JP41") (pin "1") (pinfunction "1_1") (pintype "passive"))
      (node (ref "TP41") (pin "TP") (pinfunction "TP_TP") (pintype "input"))
    )
    (net (code "42") (name "Net-(JP42-Pad1)") (class "Default")
      (node (ref "JP42") (pin "1") (pinfunction "1_1") (pintype "passive"))
      (node (ref "TP42") (pin "TP") (pinfunction "TP_TP") (pintype "input"))
    )
    (net (code "43") (name "Net-(JP43-Pad1)") (class "Default")
      (node (ref "JP43") (pin "1") (pinfunction "1_1") (pintype "passive"))
      (node (ref "TP43") (pin "TP") (pinfunction "TP_TP") (pintype "input"))
    )
    (net (code "44") (name "Net-(JP44-Pad1)") (class "Default")
      (node (ref "JP44") (pin "1") (pinfunction "1_1") (pintype "passive"))
      (node (ref "TP44") (pin "TP") (pinfunction "TP_TP") (pintype "input"))
    )
    (net (code "45") (name "Net-(JP45-Pad1)") (class "Default")
      (node (ref "JP45") (pin "1") (pinfunction "1_1") (pintype "passive"))
      (node (ref "TP45") (pin "TP") (pinfunction "TP_TP") (pintype "input"))
    )
    (net (code "46") (name "Net-(JP46-Pad1)") (class "Default")
      (node (ref "JP46") (pin "1") (pinfunction "1_1") (pintype "passive"))
      (node (ref "TP46") (pin "TP") (pinfunction "TP_TP") (pintype "input"))
    )
    (net (code "47") (name "Net-(JP47-Pad1)") (class "Default")
      (node (ref "JP47") (pin "1") (pinfunction "1_1") (pintype "passive"))
      (node (ref "TP47") (pin "TP") (pinfunction "TP_TP") (pintype "input"))
    )
    (net (code "48") (name "Net-(JP48-Pad1)") (class "Default")
      (node (ref "JP48") (pin "1") (pinfunction "1_1") (pintype "passive"))
      (node (ref "TP48") (pin "TP") (pinfunction "TP_TP") (pintype "input"))
    )
    (net (code "49") (name "Net-(JP49-Pad1)") (class "Default")
      (node (ref "JP49") (pin "1") (pinfunction "1_1") (pintype "passive"))
      (node (ref "TP49") (pin "TP") (pinfunction "TP_TP") (pintype "input"))
    )
    (net (code "50") (name "Net-(JP50-Pad1)") (class "Default")
      (node (ref "JP50") (pin "1") (pinfunction "1_1") (pintype "passive"))
      (node (ref "TP50") (pin "TP") (pinfunction "TP_TP") (pintype "input"))
    )
    (net (code "51") (name "Net-(JP51-Pad1)") (class "Default")
      (node (ref "JP51") (pin "1") (pinfunction "1_1") (pintype "passive"))
      (node (ref "TP51") (pin "TP") (pinfunction "TP_TP") (pintype "input"))
    )
    (net (code "52") (name "Net-(JP52-Pad1)") (class "Default")
      (node (ref "JP52") (pin "1") (pinfunction "1_1") (pintype "passive"))
      (node (ref "TP52") (pin "TP") (pinfunction "TP_TP") (pintype "input"))
    )
    (net (code "53") (name "Net-(JP53-Pad1)") (class "Default")
      (node (ref "JP53") (pin "1") (pinfunction "1_1") (pintype "passive"))
      (node (ref "TP53") (pin "TP") (pinfunction "TP_TP") (pintype "input"))
    )
    (net (code "54") (name "Net-(JP54-Pad1)") (class "Default")
      (node (ref "JP54") (pin "1") (pinfunction "1_1") (pintype "passive"))
      (node (ref "TP54") (pin "TP") (pinfunction "TP_TP") (pintype "input"))
    )
    (net (code "55") (name "Net-(JP55-Pad1)") (class "Default")
      (node (ref "JP55") (pin "1") (pinfunction "1_1") (pintype "passive"))
      (node (ref "TP55") (pin "TP") (pinfunction "TP_TP") (pintype "input"))
    )
    (net (code "56") (name "Net-(JP56-Pad1)") (class "Default")
      (node (ref "JP56") (pin "1") (pinfunction "1_1") (pintype "passive"))
      (node (ref "TP56") (pin "TP") (pinfunction "TP_TP") (pintype "input"))
    )
    (net (code "57") (name "Net-(JP57-Pad1)") (class "Default")
      (node (ref "JP57") (pin "1") (pinfunction "1_1") (pintype "passive"))
      (node (ref "TP57") (pin "TP") (pinfunction "TP_TP") (pintype "input"))
    )
    (net (code "58") (name "Net-(JP58-Pad1)") (class "Default")
      (node (ref "JP58") (pin "1") (pinfunction "1_1") (pintype "passive"))
      (node (ref "TP58") (pin "TP") (pinfunction "TP_TP") (pintype "input"))
    )
    (net (code "59") (name "Net-(JP59-Pad1)") (class "Default")
      (node (ref "JP59") (pin "1") (pinfunction "1_1") (pintype "passive"))
      (node (ref "TP59") (pin "TP") (pinfunction "TP_TP") (pintype "input"))
    )
    (net (code "60") (name "Net-(JP60-Pad1)") (class "Default")
      (node (ref "JP60") (pin "1") (pinfunction "1_1") (pintype "passive"))
      (node (ref "TP60") (pin "TP") (pinfunction "TP_TP") (pintype "input"))
    )
    (net (code "61") (name "Net-(JP61-Pad1)") (class "Default")
      (node (ref "JP61") (pin "1") (pinfunction "1_1") (pintype "passive"))
      (node (ref "TP61") (pin "TP") (pinfunction "TP_TP") (pintype "input"))
    )
    (net (code "62") (name "Net-(JP62-Pad1)") (class "Default")
      (node (ref "JP62") (pin "1") (pinfunction "1_1") (pintype "passive"))
      (node (ref "TP62") (pin "TP") (pinfunction "TP_TP") (pintype "input"))
    )
    (net (code "63") (name "Net-(JP63-Pad1)") (class "Default")
      (node (ref "JP63") (pin "1") (pinfunction "1_1") (pintype "passive"))
      (node (ref "TP63") (pin "TP") (pinfunction "TP_TP") (pintype "input"))
    )
    (net (code "64") (name "Net-(JP64-Pad1)") (class "Default")
      (node (ref "JP64") (pin "1") (pinfunction "1_1") (pintype "passive"))
      (node (ref "TP64") (pin "TP") (pinfunction "TP_TP") (pintype "input"))
    )
    (net (code "65") (name "Net-(JP65-Pad1)") (class "Default")
      (node (ref "JP65") (pin "1") (pinfunction "1_1") (pintype "passive"))
      (node (ref "TP65") (pin "TP") (pinfunction "TP_TP") (pintype "input"))
    )
    (net (code "66") (name "Net-(JP66-Pad1)") (class "Default")
      (node (ref "JP66") (pin "1") (pinfunction "1_1") (pintype "passive"))
      (node (ref "TP66") (pin "TP") (pinfunction "TP_TP") (pintype "input"))
    )
    (net (code "67") (name "Net-(JP67-Pad1)") (class "Default")
      (node (ref "JP67") (pin "1") (pinfunction "1_1") (pintype "passive"))
      (node (ref "TP67") (pin "TP") (pinfunction "TP_TP") (pintype "input"))
    )
    (net (code "68") (name "Net-(JP68-Pad1)") (class "Default")
      (node (ref "JP68") (pin "1") (pinfunction "1_1") (pintype "passive"))
      (node (ref "TP68") (pin "TP") (pinfunction "TP_TP") (pintype "input"))
    )
    (net (code "69") (name "Net-(JP69-Pad1)") (class "Default")
      (node (ref "JP69") (pin "1") (pinfunction "1_1") (pintype "passive"))
      (node (ref "TP69") (pin "TP") (pinfunction "TP_TP") (pintype "input"))
    )
    (net (code "70") (name "Net-(JP70-Pad1)") (class "Default")
      (node (ref "JP70") (pin "1") (pinfunction "1_1") (pintype "passive"))
      (node (ref "TP70") (pin "TP") (pinfunction "TP_TP") (pintype "input"))
    )
    (net (code "71") (name "Net-(JP71-Pad1)") (class "Default")
      (node (ref "JP71") (pin "1") (pinfunction "1_1") (pintype "passive"))
      (node (ref "TP71") (pin "TP") (pinfunction "TP_TP") (pintype "input"))
    )
    (net (code "72") (name "Net-(JP72-Pad1)") (class "Default")
      (node (ref "JP72") (pin "1") (pinfunction "1_1") (pintype "passive"))
      (node (ref "TP72") (pin "TP") (pinfunction "TP_TP") (pintype "input"))
    )
    (net (code "73") (name "Net-(JP73-Pad1)") (class "Default")
      (node (ref "JP73") (pin "1") (pinfunction "1_1") (pintype "passive"))
      (node (ref "TP73") (pin "TP") (pinfunction "TP_TP") (pintype "input"))
    )
    (net (code "74") (name "Net-(JP74-Pad1)") (class "Default")
      (node (ref "JP74") (pin "1") (pinfunction "1_1") (pintype "passive"))
      (node (ref "TP74") (pin "TP") (pinfunction "TP_TP") (pintype "input"))
    )
    (net (code "75") (name "Net-(JP75-Pad1)") (class "Default")
      (node (ref "JP75") (pin "1") (pinfunction "1_1") (pintype "passive"))
      (node (ref "TP75") (pin "TP") (pinfunction "TP_TP") (pintype "input"))
    )
    (net (code "76") (name "Net-(JP76-Pad1)") (class "Default")
      (node (ref "JP76") (pin "1") (pinfunction "1_1") (pintype "passive"))
      (node (ref "TP76") (pin "TP") (pinfunction "TP_TP") (pintype "input"))
    )
    (net (code "77") (name "Net-(JP77-Pad1)") (class "Default")
      (node (ref "JP77") (pin "1") (pinfunction "1_1") (pintype "passive"))
      (node (ref "TP77") (pin "TP") (pinfunction "TP_TP") (pintype "input"))
    )
    (net (code "78") (name "Net-(JP78-Pad1)") (class "Default")
      (node (ref "JP78") (pin "1") (pinfunction "1_1") (pintype "passive"))
      (node (ref "TP78") (pin "TP") (pinfunction "TP_TP") (pintype "input"))
    )
    (net (code "79") (name "Net-(JP79-Pad1)") (class "Default")
      (node (ref "JP79") (pin "1") (pinfunction "1_1") (pintype "passive"))
      (node (ref "TP79") (pin "TP") (pinfunction "TP_TP") (pintype "input"))
    )
    (net (code "80") (name "Net-(JP80-Pad1)") (class "Default")
      (node (ref "JP80") (pin "1") (pinfunction "1_1") (pintype "passive"))
      (node (ref "TP80") (pin "TP") (pinfunction "TP_TP") (pintype "input"))
    )
    (net (code "81") (name "Net-(JP81-Pad1)") (class "Default")
      (node (ref "JP81") (pin "1") (pinfunction "1_1") (pintype "passive"))
      (node (ref "TP81") (pin "TP") (pinfunction "TP_TP") (pintype "input"))
    )
    (net (code "82") (name "Net-(JP82-Pad1)") (class "Default")
      (node (ref "JP82") (pin "1") (pinfunction "1_1") (pintype "passive"))
      (node (ref "TP82") (pin "TP") (pinfunction "TP_TP") (pintype "input"))
    )
    (net (code "83") (name "Net-(JP83-Pad1)") (class "Default")
      (node (ref "JP83") (pin "1") (pinfunction "1_1") (pintype "passive"))
      (node (ref "TP83") (pin "TP") (pinfunction "TP_TP") (pintype "input"))
    )
    (net (code "84") (name "Net-(JP84-Pad1)") (class "Default")
      (node (ref "JP84") (pin "1") (pinfunction "1_1") (pintype "passive"))
      (node (ref "TP84") (pin "TP") (pinfunction "TP_TP") (pintype "input"))
    )
    (net (code "85") (name "Net-(JP85-Pad1)") (class "Default")
      (node (ref "JP85") (pin "1") (pinfunction "1_1") (pintype "passive"))
      (node (ref "TP85") (pin "TP") (pinfunction "TP_TP") (pintype "input"))
    )
    (net (code "86") (name "Net-(JP86-Pad1)") (class "Default")
      (node (ref "JP86") (pin "1") (pinfunction "1_1") (pintype "passive"))
      (node (ref "TP86") (pin "TP") (pinfunction "TP_TP") (pintype "input"))
    )
    (net (code "87") (name "Net-(JP87-Pad1)") (class "Default")
      (node (ref "JP87") (pin "1") (pinfunction "1_1") (pintype "passive"))
      (node (ref "TP87") (pin "TP") (pinfunction "TP_TP") (pintype "input"))
    )
    (net (code "88") (name "Net-(JP88-Pad1)") (class "Default")
      (node (ref "JP88") (pin "1") (pinfunction "1_1") (pintype "passive"))
      (node (ref "TP88") (pin "TP") (pinfunction "TP_TP") (pintype "input"))
    )
    (net (code "89") (name "Net-(JP89-Pad1)") (class "Default")
      (node (ref "JP89") (pin "1") (pinfunction "1_1") (pintype "passive"))
      (node (ref "TP89") (pin "TP") (pinfunction "TP_TP") (pintype "input"))
    )
    (net (code "90") (name "Net-(JP90-Pad1)") (class "Default")
      (node (ref "JP90") (pin "1") (pinfunction "1_1") (pintype "passive"))
      (node (ref "TP90") (pin "TP") (pinfunction "TP_TP") (pintype "input"))
    )
    (net (code "91") (name "Net-(JP91-Pad1)") (class "Default")
      (node (ref "JP91") (pin "1") (pinfunction "1_1") (pintype "passive"))
      (node (ref "TP91") (pin "TP") (pinfunction "TP_TP") (pintype "input"))
    )
    (net (code "92") (name "Net-(JP92-Pad1)") (class "Default")
      (node (ref "JP92") (pin "1") (pinfunction "1_1") (pintype "passive"))
      (node (ref "TP92") (pin "TP") (pinfunction "TP_TP") (pintype "input"))
    )
    (net (code "93") (name "Net-(JP93-Pad1)") (class "Default")
      (node (ref "JP93") (pin "1") (pinfunction "1_1") (pintype "passive"))
      (node (ref "TP93") (pin "TP") (pinfunction "TP_TP") (pintype "input"))
    )
    (net (code "94") (name "Net-(JP94-Pad1)") (class "Default")
      (node (ref "JP94") (pin "1") (pinfunction "1_1") (pintype "passive"))
      (node (ref "TP94") (pin "TP") (pinfunction "TP_TP") (pintype "input"))
    )
    (net (code "95") (name "Net-(JP95-Pad1)") (class "Default")
      (node (ref "JP95") (pin "1") (pinfunction "1_1") (pintype "passive"))
      (node (ref "TP95") (pin "TP") (pinfunction "TP_TP") (pintype "input"))
    )
    (net (code "96") (name "Net-(JP96-Pad1)") (class "Default")
      (node (ref "JP96") (pin "1") (pinfunction "1_1") (pintype "passive"))
      (node (ref "TP96") (pin "TP") (pinfunction "TP_TP") (pintype "input"))
    )
    (net (code "97") (name "Net-(JP97-Pad1)") (class "Default")
      (node (ref "JP97") (pin "1") (pinfunction "1_1") (pintype "passive"))
      (node (ref "TP97") (pin "TP") (pinfunction "TP_TP") (pintype "input"))
    )
    (net (code "98") (name "Net-(JP98-Pad1)") (class "Default")
      (node (ref "JP98") (pin "1") (pinfunction "1_1") (pintype "passive"))
      (node (ref "TP98") (pin "TP") (pinfunction "TP_TP") (pintype "input"))
    )
    (net (code "99") (name "Net-(JP99-Pad1)") (class "Default")
      (node (ref "JP99") (pin "1") (pinfunction "1_1") (pintype "passive"))
      (node (ref "TP99") (pin "TP") (pinfunction "TP_TP") (pintype "input"))
    )
    (net (code "100") (name "Net-(JP100-Pad1)") (class "Default")
      (node (ref "JP100") (pin "1") (pinfunction "1_1") (pintype "passive"))
      (node (ref "TP100") (pin "TP") (pinfunction "TP_TP") (pintype "input"))
    )
  )
)
